# CanBusFinal.net
KiCad netlist of a schematic drawn in EAGLE
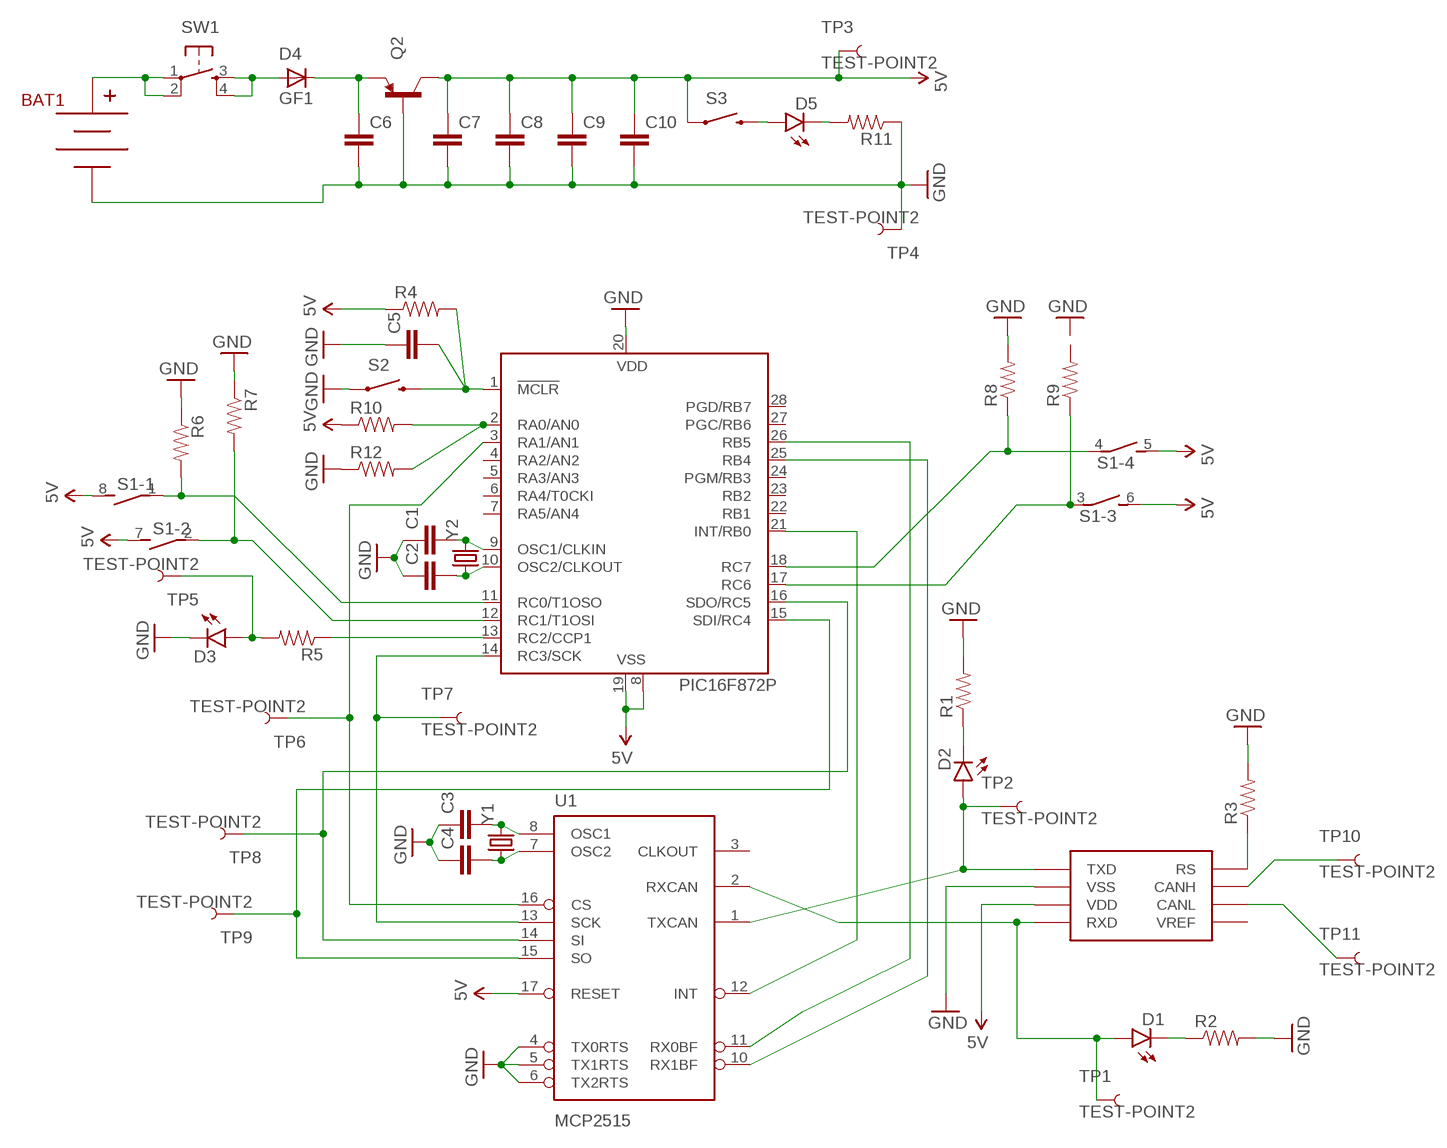
[diagram p0: schematic, sheet 1]

(export (version "E")
  (design (tool "Eeschema 10.0.6"))
  (components
    (comp (ref "BAT1")
      (value "BC9VPC")
      (footprint "eagle-import:BC9VPC")
      (libsource (lib "eagle-import") (part "BC9VPC"))
    )
    (comp (ref "C1")
      (value "CAPPTH")
      (footprint "eagle-import:CAP-PTH-SMALL")
      (libsource (lib "eagle-import") (part "CAPPTH"))
    )
    (comp (ref "C2")
      (value "CAPPTH")
      (footprint "eagle-import:CAP-PTH-SMALL")
      (libsource (lib "eagle-import") (part "CAPPTH"))
    )
    (comp (ref "C3")
      (value "CAPPTH")
      (footprint "eagle-import:CAP-PTH-SMALL")
      (libsource (lib "eagle-import") (part "CAPPTH"))
    )
    (comp (ref "C4")
      (value "CAPPTH")
      (footprint "eagle-import:CAP-PTH-SMALL")
      (libsource (lib "eagle-import") (part "CAPPTH"))
    )
    (comp (ref "C5")
      (value "CAPPTH")
      (footprint "eagle-import:CAP-PTH-SMALL")
      (libsource (lib "eagle-import") (part "CAPPTH"))
    )
    (comp (ref "C6")
      (value "CAPPTH")
      (footprint "eagle-import:CAP-PTH-SMALL")
      (libsource (lib "eagle-import") (part "CAPPTH"))
    )
    (comp (ref "C7")
      (value "CAPPTH")
      (footprint "eagle-import:CAP-PTH-SMALL")
      (libsource (lib "eagle-import") (part "CAPPTH"))
    )
    (comp (ref "C8")
      (value "CAPPTH")
      (footprint "eagle-import:CAP-PTH-SMALL")
      (libsource (lib "eagle-import") (part "CAPPTH"))
    )
    (comp (ref "C9")
      (value "CAPPTH")
      (footprint "eagle-import:CAP-PTH-SMALL")
      (libsource (lib "eagle-import") (part "CAPPTH"))
    )
    (comp (ref "C10")
      (value "CAPPTH")
      (footprint "eagle-import:CAP-PTH-SMALL")
      (libsource (lib "eagle-import") (part "CAPPTH"))
    )
    (comp (ref "D1")
      (value "LED5MM")
      (footprint "eagle-import:LED5MM")
      (libsource (lib "eagle-import") (part "LED5MM"))
    )
    (comp (ref "D2")
      (value "LED5MM")
      (footprint "eagle-import:LED5MM")
      (libsource (lib "eagle-import") (part "LED5MM"))
    )
    (comp (ref "D3")
      (value "LED5MM")
      (footprint "eagle-import:LED5MM")
      (libsource (lib "eagle-import") (part "LED5MM"))
    )
    (comp (ref "D4")
      (value "GF1")
      (footprint "eagle-import:SMA-DO214AC")
      (libsource (lib "eagle-import") (part "GF1"))
    )
    (comp (ref "D5")
      (value "LED5MM")
      (footprint "eagle-import:LED5MM")
      (libsource (lib "eagle-import") (part "LED5MM"))
    )
    (comp (ref "IC1")
      (value "PIC16F872P")
      (footprint "eagle-import:DIL28-3")
      (fields (field (name "MF") "MICROCHIP") (field (name "MPN") "PIC16F872-I/SP"))
      (libsource (lib "eagle-import") (part "PIC16872PF"))
    )
    (comp (ref "Q2")
      (value "TRANSISTOR_PNPTO92")
      (footprint "eagle-import:TO-92")
      (libsource (lib "eagle-import") (part "TRANSISTOR_PNPTO92"))
    )
    (comp (ref "R1")
      (value "RESISTOREZ")
      (footprint "eagle-import:AXIAL-0.3EZ")
      (libsource (lib "eagle-import") (part "RESISTOREZ"))
    )
    (comp (ref "R2")
      (value "RESISTOREZ")
      (footprint "eagle-import:AXIAL-0.3EZ")
      (libsource (lib "eagle-import") (part "RESISTOREZ"))
    )
    (comp (ref "R3")
      (value "RESISTOREZ")
      (footprint "eagle-import:AXIAL-0.3EZ")
      (libsource (lib "eagle-import") (part "RESISTOREZ"))
    )
    (comp (ref "R4")
      (value "RESISTOREZ")
      (footprint "eagle-import:AXIAL-0.3EZ")
      (libsource (lib "eagle-import") (part "RESISTOREZ"))
    )
    (comp (ref "R5")
      (value "RESISTOREZ")
      (footprint "eagle-import:AXIAL-0.3EZ")
      (libsource (lib "eagle-import") (part "RESISTOREZ"))
    )
    (comp (ref "R6")
      (value "RESISTOREZ")
      (footprint "eagle-import:AXIAL-0.3EZ")
      (libsource (lib "eagle-import") (part "RESISTOREZ"))
    )
    (comp (ref "R7")
      (value "RESISTOREZ")
      (footprint "eagle-import:AXIAL-0.3EZ")
      (libsource (lib "eagle-import") (part "RESISTOREZ"))
    )
    (comp (ref "R8")
      (value "RESISTOREZ")
      (footprint "eagle-import:AXIAL-0.3EZ")
      (libsource (lib "eagle-import") (part "RESISTOREZ"))
    )
    (comp (ref "R9")
      (value "RESISTOREZ")
      (footprint "eagle-import:AXIAL-0.3EZ")
      (libsource (lib "eagle-import") (part "RESISTOREZ"))
    )
    (comp (ref "R10")
      (value "RESISTOREZ")
      (footprint "eagle-import:AXIAL-0.3EZ")
      (libsource (lib "eagle-import") (part "RESISTOREZ"))
    )
    (comp (ref "R11")
      (value "RESISTOREZ")
      (footprint "eagle-import:AXIAL-0.3EZ")
      (libsource (lib "eagle-import") (part "RESISTOREZ"))
    )
    (comp (ref "R12")
      (value "RESISTORAXIAL-0.3")
      (footprint "eagle-import:AXIAL-0.3")
      (libsource (lib "eagle-import") (part "SparkFun-Resistors_RESISTORAXIAL-0.3"))
    )
    (comp (ref "S1")
      (value "DIP04S")
      (footprint "eagle-import:DIP04S")
      (libsource (lib "eagle-import") (part "DIP04S"))
    )
    (comp (ref "S2")
      (value "SWITCH-MOMENTARY-2PTH")
      (footprint "eagle-import:TACTILE-PTH")
      (libsource (lib "eagle-import") (part "SWITCH-MOMENTARY-2PTH"))
    )
    (comp (ref "S3")
      (value "SWITCH-MOMENTARY-2PTH")
      (footprint "eagle-import:TACTILE-PTH")
      (libsource (lib "eagle-import") (part "SWITCH-MOMENTARY-2PTH"))
    )
    (comp (ref "SW1")
      (value "SWITCH_SPST_4_PINSQUARE")
      (footprint "eagle-import:TACTILE-SWITCH-SMD")
      (libsource (lib "eagle-import") (part "SWITCH_SPST_4_PINSQUARE"))
    )
    (comp (ref "TP1")
      (value "TEST-POINT2")
      (footprint "eagle-import:PAD.02X.02")
      (libsource (lib "eagle-import") (part "TEST-POINT2"))
    )
    (comp (ref "TP2")
      (value "TEST-POINT2")
      (footprint "eagle-import:PAD.02X.02")
      (libsource (lib "eagle-import") (part "TEST-POINT2"))
    )
    (comp (ref "TP3")
      (value "TEST-POINT2")
      (footprint "eagle-import:PAD.02X.02")
      (libsource (lib "eagle-import") (part "TEST-POINT2"))
    )
    (comp (ref "TP4")
      (value "TEST-POINT2")
      (footprint "eagle-import:PAD.02X.02")
      (libsource (lib "eagle-import") (part "TEST-POINT2"))
    )
    (comp (ref "TP5")
      (value "TEST-POINT2")
      (footprint "eagle-import:PAD.02X.02")
      (libsource (lib "eagle-import") (part "TEST-POINT2"))
    )
    (comp (ref "TP6")
      (value "TEST-POINT2")
      (footprint "eagle-import:PAD.02X.02")
      (libsource (lib "eagle-import") (part "TEST-POINT2"))
    )
    (comp (ref "TP7")
      (value "TEST-POINT2")
      (footprint "eagle-import:PAD.02X.02")
      (libsource (lib "eagle-import") (part "TEST-POINT2"))
    )
    (comp (ref "TP8")
      (value "TEST-POINT2")
      (footprint "eagle-import:PAD.02X.02")
      (libsource (lib "eagle-import") (part "TEST-POINT2"))
    )
    (comp (ref "TP9")
      (value "TEST-POINT2")
      (footprint "eagle-import:PAD.02X.02")
      (libsource (lib "eagle-import") (part "TEST-POINT2"))
    )
    (comp (ref "TP10")
      (value "TEST-POINT2")
      (footprint "eagle-import:PAD.02X.02")
      (libsource (lib "eagle-import") (part "TEST-POINT2"))
    )
    (comp (ref "TP11")
      (value "TEST-POINT2")
      (footprint "eagle-import:PAD.02X.02")
      (libsource (lib "eagle-import") (part "TEST-POINT2"))
    )
    (comp (ref "U$1")
      (value "MCP2551")
      (footprint "eagle-import:MCP2551")
      (libsource (lib "eagle-import") (part "MCP2551"))
    )
    (comp (ref "U1")
      (value "MCP2515")
      (footprint "eagle-import:DIL18")
      (libsource (lib "eagle-import") (part "MCP2510P"))
    )
    (comp (ref "Y1")
      (value "CRYSTALHC49UV")
      (footprint "eagle-import:HC49U-V")
      (libsource (lib "eagle-import") (part "CRYSTALHC49UV"))
    )
    (comp (ref "Y2")
      (value "CRYSTALHC49UV")
      (footprint "eagle-import:HC49U-V")
      (libsource (lib "eagle-import") (part "CRYSTALHC49UV"))
    )
  )
  (nets
    (net (code "1") (name "5V") (class "Default")
      (node (ref "C10") (pin "1") (pinfunction "1_1") (pintype "passive"))
      (node (ref "C7") (pin "1") (pinfunction "1_1") (pintype "passive"))
      (node (ref "C8") (pin "1") (pinfunction "1_1") (pintype "passive"))
      (node (ref "C9") (pin "1") (pinfunction "1_1") (pintype "passive"))
      (node (ref "IC1") (pin "19") (pinfunction "VSS_19") (pintype "power_in"))
      (node (ref "IC1") (pin "8") (pinfunction "VSS_8") (pintype "power_in"))
      (node (ref "Q2") (pin "3") (pinfunction "C_3") (pintype "passive"))
      (node (ref "R10") (pin "P$1") (pinfunction "1_P$1") (pintype "passive"))
      (node (ref "R4") (pin "P$1") (pinfunction "1_P$1") (pintype "passive"))
      (node (ref "S1") (pin "5") (pinfunction "2_5") (pintype "passive"))
      (node (ref "S1") (pin "6") (pinfunction "2_6") (pintype "passive"))
      (node (ref "S1") (pin "7") (pinfunction "2_7") (pintype "passive"))
      (node (ref "S1") (pin "8") (pinfunction "2_8") (pintype "passive"))
      (node (ref "S3") (pin "1") (pinfunction "1_1") (pintype "passive"))
      (node (ref "TP3") (pin "P$1") (pinfunction "1_P$1") (pintype "bidirectional"))
      (node (ref "U$1") (pin "VDD") (pinfunction "VDD_VDD") (pintype "bidirectional"))
      (node (ref "U1") (pin "17") (pinfunction "RESET_17") (pintype "input"))
    )
    (net (code "2") (name "GND") (class "Default")
      (node (ref "BAT1") (pin "V-") (pinfunction "V-_V-") (pintype "bidirectional"))
      (node (ref "C1") (pin "1") (pinfunction "1_1") (pintype "passive"))
      (node (ref "C10") (pin "2") (pinfunction "2_2") (pintype "passive"))
      (node (ref "C2") (pin "1") (pinfunction "1_1") (pintype "passive"))
      (node (ref "C3") (pin "1") (pinfunction "1_1") (pintype "passive"))
      (node (ref "C4") (pin "1") (pinfunction "1_1") (pintype "passive"))
      (node (ref "C5") (pin "1") (pinfunction "1_1") (pintype "passive"))
      (node (ref "C6") (pin "2") (pinfunction "2_2") (pintype "passive"))
      (node (ref "C7") (pin "2") (pinfunction "2_2") (pintype "passive"))
      (node (ref "C8") (pin "2") (pinfunction "2_2") (pintype "passive"))
      (node (ref "C9") (pin "2") (pinfunction "2_2") (pintype "passive"))
      (node (ref "D3") (pin "K") (pinfunction "C_K") (pintype "passive"))
      (node (ref "IC1") (pin "20") (pinfunction "VDD_20") (pintype "power_in"))
      (node (ref "Q2") (pin "2") (pinfunction "B_2") (pintype "passive"))
      (node (ref "R1") (pin "P$2") (pinfunction "2_P$2") (pintype "passive"))
      (node (ref "R11") (pin "P$1") (pinfunction "1_P$1") (pintype "passive"))
      (node (ref "R12") (pin "P$1") (pinfunction "1_P$1") (pintype "passive"))
      (node (ref "R2") (pin "P$2") (pinfunction "2_P$2") (pintype "passive"))
      (node (ref "R3") (pin "P$2") (pinfunction "2_P$2") (pintype "passive"))
      (node (ref "R6") (pin "P$1") (pinfunction "1_P$1") (pintype "passive"))
      (node (ref "R7") (pin "P$1") (pinfunction "1_P$1") (pintype "passive"))
      (node (ref "R8") (pin "P$2") (pinfunction "2_P$2") (pintype "passive"))
      (node (ref "S2") (pin "1") (pinfunction "1_1") (pintype "passive"))
      (node (ref "TP4") (pin "P$1") (pinfunction "1_P$1") (pintype "bidirectional"))
      (node (ref "U$1") (pin "VSS") (pinfunction "VSS_VSS") (pintype "bidirectional"))
      (node (ref "U1") (pin "4") (pinfunction "TX0RTS_4") (pintype "input"))
      (node (ref "U1") (pin "5") (pinfunction "TX1RTS_5") (pintype "input"))
      (node (ref "U1") (pin "6") (pinfunction "TX2RTS_6") (pintype "input"))
    )
    (net (code "3") (name "Net-(BAT1-PadV+)") (class "Default")
      (node (ref "BAT1") (pin "V+") (pinfunction "V+_V+") (pintype "bidirectional"))
      (node (ref "SW1") (pin "1") (pinfunction "1_1") (pintype "passive"))
      (node (ref "SW1") (pin "2") (pinfunction "2_2") (pintype "passive"))
    )
    (net (code "4") (name "Net-(D1-C)") (class "Default")
      (node (ref "D1") (pin "K") (pinfunction "C_K") (pintype "passive"))
      (node (ref "R2") (pin "P$1") (pinfunction "1_P$1") (pintype "passive"))
    )
    (net (code "5") (name "Net-(D2-C)") (class "Default")
      (node (ref "D2") (pin "K") (pinfunction "C_K") (pintype "passive"))
      (node (ref "R1") (pin "P$1") (pinfunction "1_P$1") (pintype "passive"))
    )
    (net (code "6") (name "Net-(D4-C)") (class "Default")
      (node (ref "C6") (pin "1") (pinfunction "1_1") (pintype "passive"))
      (node (ref "D4") (pin "K") (pinfunction "C_K") (pintype "passive"))
      (node (ref "Q2") (pin "1") (pinfunction "E_1") (pintype "passive"))
    )
    (net (code "7") (name "Net-(D4-PadA)") (class "Default")
      (node (ref "D4") (pin "A") (pinfunction "A_A") (pintype "passive"))
      (node (ref "SW1") (pin "3") (pinfunction "3_3") (pintype "passive"))
      (node (ref "SW1") (pin "4") (pinfunction "4_4") (pintype "passive"))
    )
    (net (code "8") (name "Net-(D5-C)") (class "Default")
      (node (ref "D5") (pin "K") (pinfunction "C_K") (pintype "passive"))
      (node (ref "R11") (pin "P$2") (pinfunction "2_P$2") (pintype "passive"))
    )
    (net (code "9") (name "Net-(IC1-INT{slash}RB0)") (class "Default")
      (node (ref "IC1") (pin "21") (pinfunction "INT/RB0_21") (pintype "bidirectional"))
      (node (ref "U1") (pin "12") (pinfunction "INT_12") (pintype "output"))
    )
    (net (code "10") (name "Net-(IC1-OSC1{slash}CLKIN)") (class "Default")
      (node (ref "C1") (pin "2") (pinfunction "2_2") (pintype "passive"))
      (node (ref "IC1") (pin "9") (pinfunction "OSC1/CLKIN_9") (pintype "input"))
      (node (ref "Y2") (pin "2") (pinfunction "2_2") (pintype "passive"))
    )
    (net (code "11") (name "Net-(IC1-OSC2{slash}CLKOUT)") (class "Default")
      (node (ref "C2") (pin "2") (pinfunction "2_2") (pintype "passive"))
      (node (ref "IC1") (pin "10") (pinfunction "OSC2/CLKOUT_10") (pintype "output"))
      (node (ref "Y2") (pin "1") (pinfunction "1_1") (pintype "passive"))
    )
    (net (code "12") (name "Net-(IC1-RA0{slash}AN0)") (class "Default")
      (node (ref "IC1") (pin "2") (pinfunction "RA0/AN0_2") (pintype "bidirectional"))
      (node (ref "R10") (pin "P$2") (pinfunction "2_P$2") (pintype "passive"))
      (node (ref "R12") (pin "P$2") (pinfunction "2_P$2") (pintype "passive"))
    )
    (net (code "13") (name "Net-(IC1-RA1{slash}AN1)") (class "Default")
      (node (ref "IC1") (pin "3") (pinfunction "RA1/AN1_3") (pintype "bidirectional"))
      (node (ref "TP6") (pin "P$1") (pinfunction "1_P$1") (pintype "bidirectional"))
      (node (ref "U1") (pin "16") (pinfunction "CS_16") (pintype "input"))
    )
    (net (code "14") (name "Net-(IC1-RB4)") (class "Default")
      (node (ref "IC1") (pin "25") (pinfunction "RB4_25") (pintype "bidirectional"))
      (node (ref "U1") (pin "10") (pinfunction "RX1BF_10") (pintype "output"))
    )
    (net (code "15") (name "Net-(IC1-RB5)") (class "Default")
      (node (ref "IC1") (pin "26") (pinfunction "RB5_26") (pintype "bidirectional"))
      (node (ref "U1") (pin "11") (pinfunction "RX0BF_11") (pintype "output"))
    )
    (net (code "16") (name "Net-(IC1-RC0{slash}T1OSO)") (class "Default")
      (node (ref "IC1") (pin "11") (pinfunction "RC0/T1OSO_11") (pintype "bidirectional"))
      (node (ref "R6") (pin "P$2") (pinfunction "2_P$2") (pintype "passive"))
      (node (ref "S1") (pin "1") (pinfunction "1_1") (pintype "passive"))
    )
    (net (code "17") (name "Net-(IC1-RC1{slash}T1OSI)") (class "Default")
      (node (ref "IC1") (pin "12") (pinfunction "RC1/T1OSI_12") (pintype "bidirectional"))
      (node (ref "R7") (pin "P$2") (pinfunction "2_P$2") (pintype "passive"))
      (node (ref "S1") (pin "2") (pinfunction "1_2") (pintype "passive"))
    )
    (net (code "18") (name "Net-(IC1-RC2{slash}CCP1)") (class "Default")
      (node (ref "IC1") (pin "13") (pinfunction "RC2/CCP1_13") (pintype "bidirectional"))
      (node (ref "R5") (pin "P$1") (pinfunction "1_P$1") (pintype "passive"))
    )
    (net (code "19") (name "Net-(IC1-RC3{slash}SCK)") (class "Default")
      (node (ref "IC1") (pin "14") (pinfunction "RC3/SCK_14") (pintype "bidirectional"))
      (node (ref "TP7") (pin "P$1") (pinfunction "1_P$1") (pintype "bidirectional"))
      (node (ref "U1") (pin "13") (pinfunction "SCK_13") (pintype "input"))
    )
    (net (code "20") (name "Net-(IC1-RC6)") (class "Default")
      (node (ref "IC1") (pin "17") (pinfunction "RC6_17") (pintype "bidirectional"))
      (node (ref "R9") (pin "P$1") (pinfunction "1_P$1") (pintype "passive"))
      (node (ref "S1") (pin "3") (pinfunction "1_3") (pintype "passive"))
    )
    (net (code "21") (name "Net-(IC1-RC7)") (class "Default")
      (node (ref "IC1") (pin "18") (pinfunction "RC7_18") (pintype "bidirectional"))
      (node (ref "R8") (pin "P$1") (pinfunction "1_P$1") (pintype "passive"))
      (node (ref "S1") (pin "4") (pinfunction "1_4") (pintype "passive"))
    )
    (net (code "22") (name "Net-(IC1-SDI{slash}RC4)") (class "Default")
      (node (ref "IC1") (pin "15") (pinfunction "SDI/RC4_15") (pintype "bidirectional"))
      (node (ref "TP9") (pin "P$1") (pinfunction "1_P$1") (pintype "bidirectional"))
      (node (ref "U1") (pin "15") (pinfunction "SO_15") (pintype "output"))
    )
    (net (code "23") (name "Net-(IC1-SDO{slash}RC5)") (class "Default")
      (node (ref "IC1") (pin "16") (pinfunction "SDO/RC5_16") (pintype "bidirectional"))
      (node (ref "TP8") (pin "P$1") (pinfunction "1_P$1") (pintype "bidirectional"))
      (node (ref "U1") (pin "14") (pinfunction "SI_14") (pintype "input"))
    )
    (net (code "24") (name "Net-(IC1-~{MCLR})") (class "Default")
      (node (ref "C5") (pin "2") (pinfunction "2_2") (pintype "passive"))
      (node (ref "IC1") (pin "1") (pinfunction "~{MCLR}_1") (pintype "input"))
      (node (ref "R4") (pin "P$2") (pinfunction "2_P$2") (pintype "passive"))
      (node (ref "S2") (pin "3") (pinfunction "2_3") (pintype "passive"))
    )
    (net (code "25") (name "Net-(R3-1)") (class "Default")
      (node (ref "R3") (pin "P$1") (pinfunction "1_P$1") (pintype "passive"))
      (node (ref "U$1") (pin "RS") (pinfunction "RS_RS") (pintype "bidirectional"))
    )
    (net (code "26") (name "Net-(R5-2)") (class "Default")
      (node (ref "D3") (pin "A") (pinfunction "A_A") (pintype "passive"))
      (node (ref "R5") (pin "P$2") (pinfunction "2_P$2") (pintype "passive"))
      (node (ref "TP5") (pin "P$1") (pinfunction "1_P$1") (pintype "bidirectional"))
    )
    (net (code "27") (name "Net-(S3-2)") (class "Default")
      (node (ref "D5") (pin "A") (pinfunction "A_A") (pintype "passive"))
      (node (ref "S3") (pin "3") (pinfunction "2_3") (pintype "passive"))
    )
    (net (code "28") (name "Net-(TP1-1)") (class "Default")
      (node (ref "D1") (pin "A") (pinfunction "A_A") (pintype "passive"))
      (node (ref "TP1") (pin "P$1") (pinfunction "1_P$1") (pintype "bidirectional"))
      (node (ref "U$1") (pin "RXD") (pinfunction "RXD_RXD") (pintype "bidirectional"))
      (node (ref "U1") (pin "2") (pinfunction "RXCAN_2") (pintype "input"))
    )
    (net (code "29") (name "Net-(TP2-1)") (class "Default")
      (node (ref "D2") (pin "A") (pinfunction "A_A") (pintype "passive"))
      (node (ref "TP2") (pin "P$1") (pinfunction "1_P$1") (pintype "bidirectional"))
      (node (ref "U$1") (pin "TXD") (pinfunction "TXD_TXD") (pintype "bidirectional"))
      (node (ref "U1") (pin "1") (pinfunction "TXCAN_1") (pintype "output"))
    )
    (net (code "30") (name "Net-(TP10-1)") (class "Default")
      (node (ref "TP10") (pin "P$1") (pinfunction "1_P$1") (pintype "bidirectional"))
      (node (ref "U$1") (pin "CANH") (pinfunction "CANH_CANH") (pintype "bidirectional"))
    )
    (net (code "31") (name "Net-(TP11-1)") (class "Default")
      (node (ref "TP11") (pin "P$1") (pinfunction "1_P$1") (pintype "bidirectional"))
      (node (ref "U$1") (pin "CANL") (pinfunction "CANL_CANL") (pintype "bidirectional"))
    )
    (net (code "32") (name "Net-(U1A-OSC1)") (class "Default")
      (node (ref "C3") (pin "2") (pinfunction "2_2") (pintype "passive"))
      (node (ref "U1") (pin "8") (pinfunction "OSC1_8") (pintype "input"))
      (node (ref "Y1") (pin "2") (pinfunction "2_2") (pintype "passive"))
    )
    (net (code "33") (name "Net-(U1A-OSC2)") (class "Default")
      (node (ref "C4") (pin "2") (pinfunction "2_2") (pintype "passive"))
      (node (ref "U1") (pin "7") (pinfunction "OSC2_7") (pintype "output"))
      (node (ref "Y1") (pin "1") (pinfunction "1_1") (pintype "passive"))
    )
    (net (code "34") (name "unconnected-(IC1-PGC{slash}RB6-Pad27)") (class "Default")
      (node (ref "IC1") (pin "27") (pinfunction "PGC/RB6_27") (pintype "bidirectional"))
    )
    (net (code "35") (name "unconnected-(IC1-PGD{slash}RB7-Pad28)") (class "Default")
      (node (ref "IC1") (pin "28") (pinfunction "PGD/RB7_28") (pintype "bidirectional"))
    )
    (net (code "36") (name "unconnected-(IC1-PGM{slash}RB3-Pad24)") (class "Default")
      (node (ref "IC1") (pin "24") (pinfunction "PGM/RB3_24") (pintype "bidirectional"))
    )
    (net (code "37") (name "unconnected-(IC1-RA2{slash}AN2-Pad4)") (class "Default")
      (node (ref "IC1") (pin "4") (pinfunction "RA2/AN2_4") (pintype "bidirectional"))
    )
    (net (code "38") (name "unconnected-(IC1-RA3{slash}AN3-Pad5)") (class "Default")
      (node (ref "IC1") (pin "5") (pinfunction "RA3/AN3_5") (pintype "bidirectional"))
    )
    (net (code "39") (name "unconnected-(IC1-RA4{slash}T0CKI-Pad6)") (class "Default")
      (node (ref "IC1") (pin "6") (pinfunction "RA4/T0CKI_6") (pintype "bidirectional"))
    )
    (net (code "40") (name "unconnected-(IC1-RA5{slash}AN4-Pad7)") (class "Default")
      (node (ref "IC1") (pin "7") (pinfunction "RA5/AN4_7") (pintype "bidirectional"))
    )
    (net (code "41") (name "unconnected-(IC1-RB1-Pad22)") (class "Default")
      (node (ref "IC1") (pin "22") (pinfunction "RB1_22") (pintype "bidirectional"))
    )
    (net (code "42") (name "unconnected-(IC1-RB2-Pad23)") (class "Default")
      (node (ref "IC1") (pin "23") (pinfunction "RB2_23") (pintype "bidirectional"))
    )
    (net (code "43") (name "unconnected-(R9-2-PadP$2)") (class "Default")
      (node (ref "R9") (pin "P$2") (pinfunction "2_P$2") (pintype "passive"))
    )
    (net (code "44") (name "unconnected-(U$1-PadVREF)") (class "Default")
      (node (ref "U$1") (pin "VREF") (pinfunction "VREF_VREF") (pintype "bidirectional"))
    )
    (net (code "45") (name "unconnected-(U1A-CLKOUT-Pad3)") (class "Default")
      (node (ref "U1") (pin "3") (pinfunction "CLKOUT_3") (pintype "output"))
    )
  )
)
